# arduinoVisor.net
KiCad netlist of a schematic drawn in EAGLE
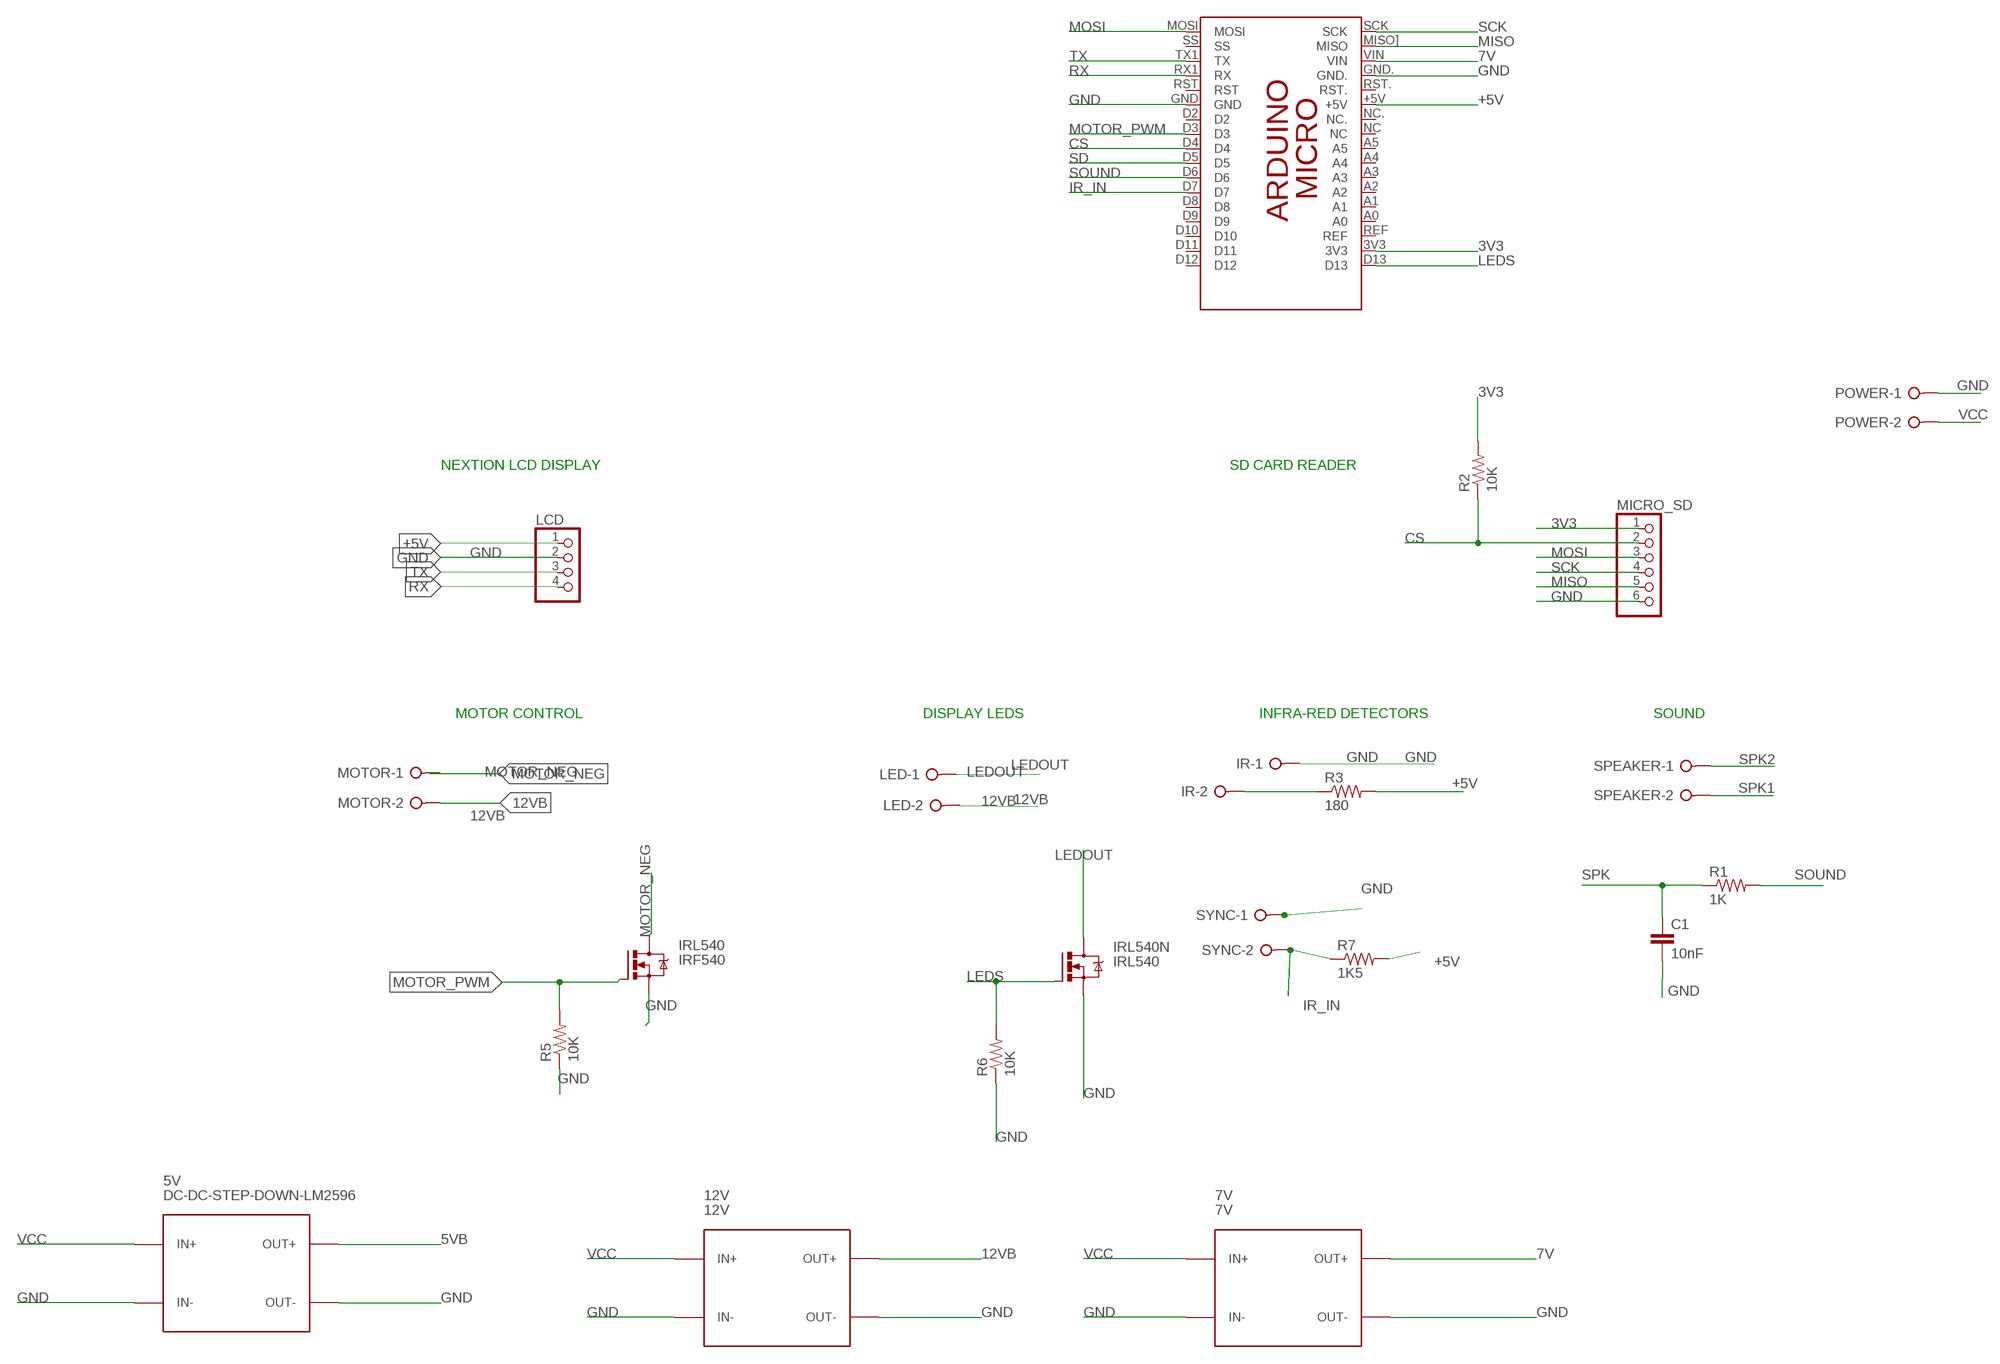
[diagram p0: schematic, sheet 1]
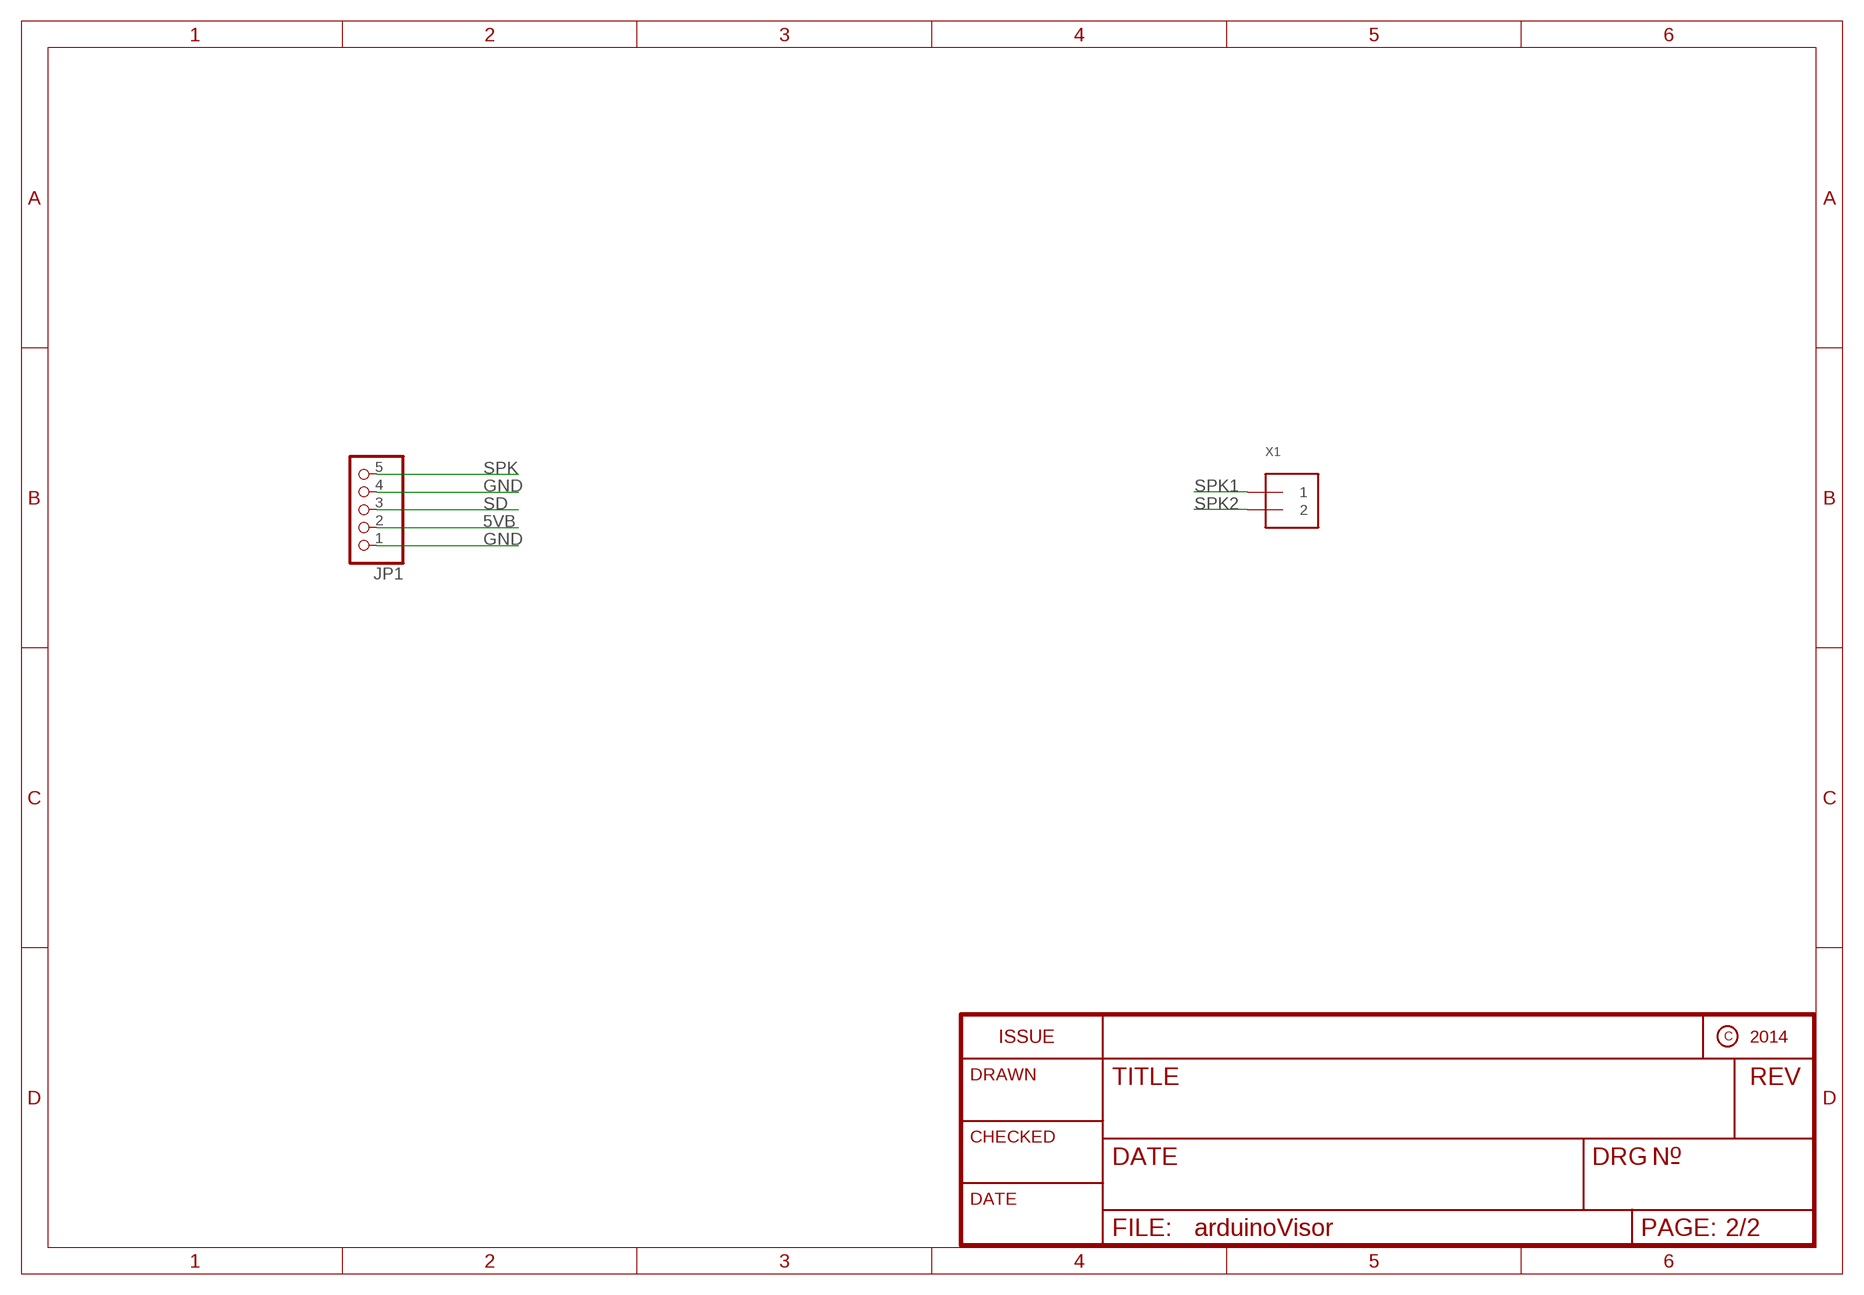
[diagram p1: schematic, sheet 2]

(export (version "E")
  (design (tool "Eeschema 10.0.6"))
  (components
    (comp (ref "JP1")
      (value "HEADER-1X570MIL")
      (footprint "eagle-import:1X05_ROUND_70")
      (libsource (lib "eagle-import") (part "HEADER-1X570MIL"))
    )
    (comp (ref "X1")
      (value "TERMBLOCK_1X2")
      (footprint "eagle-import:TERMBLOCK_1X2-3.5MM")
      (libsource (lib "eagle-import") (part "TERMBLOCK_1X2"))
    )
    (comp (ref "5V")
      (value "DC-DC-STEP-DOWN-LM2596")
      (footprint "eagle-import:DC-DC-STEP-DOWN-LM2596")
      (libsource (lib "eagle-import") (part "DC-DC-STEP-DOWN-LM2596"))
    )
    (comp (ref "7V")
      (value "7V")
      (footprint "eagle-import:DC-DC-STEP-DOWN-LM2596")
      (libsource (lib "eagle-import") (part "DC-DC-STEP-DOWN-LM2596"))
    )
    (comp (ref "12V")
      (value "12V")
      (footprint "eagle-import:DC-DC-STEP-DOWN-LM2596")
      (libsource (lib "eagle-import") (part "DC-DC-STEP-DOWN-LM2596"))
    )
    (comp (ref "C1")
      (value "10nF")
      (footprint "eagle-import:C2.5-2")
      (libsource (lib "eagle-import") (part "C2.5/2"))
    )
    (comp (ref "IR")
      (value "W237-02P")
      (footprint "eagle-import:W237-132")
      (libsource (lib "eagle-import") (part "W237-02P"))
    )
    (comp (ref "IRL540")
      (value "IRF540")
      (footprint "eagle-import:TO220BV")
      (libsource (lib "eagle-import") (part "IRF540"))
    )
    (comp (ref "IRL540N")
      (value "IRL540")
      (footprint "eagle-import:TO220BV")
      (libsource (lib "eagle-import") (part "IRF540"))
    )
    (comp (ref "LCD")
      (value "PINHD-1X4")
      (footprint "eagle-import:1X04")
      (libsource (lib "eagle-import") (part "PINHD-1X4"))
    )
    (comp (ref "LED")
      (value "W237-02P")
      (footprint "eagle-import:W237-132")
      (libsource (lib "eagle-import") (part "W237-02P"))
    )
    (comp (ref "MICRO_SD")
      (value "PINHD-1X6")
      (footprint "eagle-import:1X06")
      (libsource (lib "eagle-import") (part "PINHD-1X6"))
    )
    (comp (ref "MOTOR")
      (value "W237-02P")
      (footprint "eagle-import:W237-132")
      (libsource (lib "eagle-import") (part "W237-02P"))
    )
    (comp (ref "PCB2")
      (value "ARDUINO_MICRO")
      (footprint "eagle-import:ARDUINO_MICRO")
      (libsource (lib "eagle-import") (part "ARDUINO_MICRO"))
    )
    (comp (ref "POWER")
      (value "W237-02P")
      (footprint "eagle-import:W237-132")
      (libsource (lib "eagle-import") (part "W237-02P"))
    )
    (comp (ref "R1")
      (value "1K")
      (footprint "eagle-import:0207_10")
      (libsource (lib "eagle-import") (part "R-US_0207/10"))
    )
    (comp (ref "R2")
      (value "10K")
      (footprint "eagle-import:0207_10")
      (libsource (lib "eagle-import") (part "R-US_0207/10"))
    )
    (comp (ref "R3")
      (value "180")
      (footprint "eagle-import:0207_10")
      (libsource (lib "eagle-import") (part "R-US_0207/10"))
    )
    (comp (ref "R5")
      (value "10K")
      (footprint "eagle-import:0207_10")
      (libsource (lib "eagle-import") (part "R-US_0207/10"))
    )
    (comp (ref "R6")
      (value "10K")
      (footprint "eagle-import:0207_10")
      (libsource (lib "eagle-import") (part "R-US_0207/10"))
    )
    (comp (ref "R7")
      (value "1K5")
      (footprint "eagle-import:0207_10")
      (libsource (lib "eagle-import") (part "R-US_0207/10"))
    )
    (comp (ref "SPEAKER")
      (value "W237-02P")
      (footprint "eagle-import:W237-132")
      (libsource (lib "eagle-import") (part "W237-02P"))
    )
    (comp (ref "SYNC")
      (value "W237-02P")
      (footprint "eagle-import:W237-132")
      (libsource (lib "eagle-import") (part "W237-02P"))
    )
  )
  (nets
    (net (code "1") (name "+5V") (class "Default")
      (node (ref "LCD") (pin "1") (pinfunction "1_1") (pintype "passive"))
      (node (ref "PCB2") (pin "+5V") (pinfunction "+5V_+5V") (pintype "bidirectional"))
      (node (ref "R3") (pin "2") (pinfunction "2_2") (pintype "passive"))
      (node (ref "R7") (pin "2") (pinfunction "2_2") (pintype "passive"))
    )
    (net (code "2") (name "3V3") (class "Default")
      (node (ref "MICRO_SD") (pin "1") (pinfunction "1_1") (pintype "passive"))
      (node (ref "PCB2") (pin "3V3") (pinfunction "3V3_3V3") (pintype "bidirectional"))
      (node (ref "R2") (pin "2") (pinfunction "2_2") (pintype "passive"))
    )
    (net (code "3") (name "5VB") (class "Default")
      (node (ref "5V") (pin "OUT+") (pinfunction "OUT+_OUT+") (pintype "bidirectional"))
      (node (ref "JP1") (pin "2") (pinfunction "2_2") (pintype "passive"))
    )
    (net (code "4") (name "7V") (class "Default")
      (node (ref "7V") (pin "OUT+") (pinfunction "OUT+_OUT+") (pintype "bidirectional"))
      (node (ref "PCB2") (pin "VIN") (pinfunction "VIN_VIN") (pintype "bidirectional"))
    )
    (net (code "5") (name "12VB") (class "Default")
      (node (ref "12V") (pin "OUT+") (pinfunction "OUT+_OUT+") (pintype "bidirectional"))
      (node (ref "LED") (pin "2") (pinfunction "KL_2") (pintype "passive"))
      (node (ref "MOTOR") (pin "2") (pinfunction "KL_2") (pintype "passive"))
    )
    (net (code "6") (name "CS") (class "Default")
      (node (ref "MICRO_SD") (pin "2") (pinfunction "2_2") (pintype "passive"))
      (node (ref "PCB2") (pin "D4") (pinfunction "D4_D4") (pintype "bidirectional"))
      (node (ref "R2") (pin "1") (pinfunction "1_1") (pintype "passive"))
    )
    (net (code "7") (name "GND") (class "Default")
      (node (ref "12V") (pin "IN-") (pinfunction "IN-_IN-") (pintype "bidirectional"))
      (node (ref "12V") (pin "OUT-") (pinfunction "OUT-_OUT-") (pintype "bidirectional"))
      (node (ref "5V") (pin "IN-") (pinfunction "IN-_IN-") (pintype "bidirectional"))
      (node (ref "5V") (pin "OUT-") (pinfunction "OUT-_OUT-") (pintype "bidirectional"))
      (node (ref "7V") (pin "IN-") (pinfunction "IN-_IN-") (pintype "bidirectional"))
      (node (ref "7V") (pin "OUT-") (pinfunction "OUT-_OUT-") (pintype "bidirectional"))
      (node (ref "C1") (pin "2") (pinfunction "2_2") (pintype "passive"))
      (node (ref "IR") (pin "1") (pinfunction "KL_1") (pintype "passive"))
      (node (ref "IRL540") (pin "S") (pinfunction "S_S") (pintype "passive"))
      (node (ref "IRL540N") (pin "S") (pinfunction "S_S") (pintype "passive"))
      (node (ref "JP1") (pin "1") (pinfunction "1_1") (pintype "passive"))
      (node (ref "JP1") (pin "4") (pinfunction "4_4") (pintype "passive"))
      (node (ref "LCD") (pin "2") (pinfunction "2_2") (pintype "passive"))
      (node (ref "MICRO_SD") (pin "6") (pinfunction "6_6") (pintype "passive"))
      (node (ref "PCB2") (pin "GND") (pinfunction "GND_GND") (pintype "bidirectional"))
      (node (ref "PCB2") (pin "GND.") (pinfunction "GND._GND.") (pintype "bidirectional"))
      (node (ref "POWER") (pin "1") (pinfunction "KL_1") (pintype "passive"))
      (node (ref "R5") (pin "1") (pinfunction "1_1") (pintype "passive"))
      (node (ref "R6") (pin "1") (pinfunction "1_1") (pintype "passive"))
      (node (ref "SYNC") (pin "1") (pinfunction "KL_1") (pintype "passive"))
    )
    (net (code "8") (name "IR_IN") (class "Default")
      (node (ref "PCB2") (pin "D7") (pinfunction "D7_D7") (pintype "bidirectional"))
      (node (ref "R7") (pin "1") (pinfunction "1_1") (pintype "passive"))
      (node (ref "SYNC") (pin "2") (pinfunction "KL_2") (pintype "passive"))
    )
    (net (code "9") (name "LEDOUT") (class "Default")
      (node (ref "IRL540N") (pin "D") (pinfunction "D_D") (pintype "passive"))
      (node (ref "LED") (pin "1") (pinfunction "KL_1") (pintype "passive"))
    )
    (net (code "10") (name "LEDS") (class "Default")
      (node (ref "IRL540N") (pin "G") (pinfunction "G_G") (pintype "passive"))
      (node (ref "PCB2") (pin "D13") (pinfunction "D13_D13") (pintype "bidirectional"))
      (node (ref "R6") (pin "2") (pinfunction "2_2") (pintype "passive"))
    )
    (net (code "11") (name "MISO") (class "Default")
      (node (ref "MICRO_SD") (pin "5") (pinfunction "5_5") (pintype "passive"))
      (node (ref "PCB2") (pin "MISO]") (pinfunction "MISO_MISO]") (pintype "bidirectional"))
    )
    (net (code "12") (name "MOSI") (class "Default")
      (node (ref "MICRO_SD") (pin "3") (pinfunction "3_3") (pintype "passive"))
      (node (ref "PCB2") (pin "MOSI") (pinfunction "MOSI_MOSI") (pintype "bidirectional"))
    )
    (net (code "13") (name "MOTOR_NEG") (class "Default")
      (node (ref "IRL540") (pin "D") (pinfunction "D_D") (pintype "passive"))
      (node (ref "MOTOR") (pin "1") (pinfunction "KL_1") (pintype "passive"))
    )
    (net (code "14") (name "MOTOR_PWM") (class "Default")
      (node (ref "IRL540") (pin "G") (pinfunction "G_G") (pintype "passive"))
      (node (ref "PCB2") (pin "D3") (pinfunction "D3_D3") (pintype "bidirectional"))
      (node (ref "R5") (pin "2") (pinfunction "2_2") (pintype "passive"))
    )
    (net (code "15") (name "Net-(IRB-KL)") (class "Default")
      (node (ref "IR") (pin "2") (pinfunction "KL_2") (pintype "passive"))
      (node (ref "R3") (pin "1") (pinfunction "1_1") (pintype "passive"))
    )
    (net (code "16") (name "RX") (class "Default")
      (node (ref "LCD") (pin "4") (pinfunction "4_4") (pintype "passive"))
      (node (ref "PCB2") (pin "RX1") (pinfunction "RX_RX1") (pintype "bidirectional"))
    )
    (net (code "17") (name "SCK") (class "Default")
      (node (ref "MICRO_SD") (pin "4") (pinfunction "4_4") (pintype "passive"))
      (node (ref "PCB2") (pin "SCK") (pinfunction "SCK_SCK") (pintype "bidirectional"))
    )
    (net (code "18") (name "SD") (class "Default")
      (node (ref "JP1") (pin "3") (pinfunction "3_3") (pintype "passive"))
      (node (ref "PCB2") (pin "D5") (pinfunction "D5_D5") (pintype "bidirectional"))
    )
    (net (code "19") (name "SOUND") (class "Default")
      (node (ref "PCB2") (pin "D6") (pinfunction "D6_D6") (pintype "bidirectional"))
      (node (ref "R1") (pin "2") (pinfunction "2_2") (pintype "passive"))
    )
    (net (code "20") (name "SPK") (class "Default")
      (node (ref "C1") (pin "1") (pinfunction "1_1") (pintype "passive"))
      (node (ref "JP1") (pin "5") (pinfunction "5_5") (pintype "passive"))
      (node (ref "R1") (pin "1") (pinfunction "1_1") (pintype "passive"))
    )
    (net (code "21") (name "SPK1") (class "Default")
      (node (ref "SPEAKER") (pin "2") (pinfunction "KL_2") (pintype "passive"))
      (node (ref "X1") (pin "1") (pinfunction "1_1") (pintype "passive"))
    )
    (net (code "22") (name "SPK2") (class "Default")
      (node (ref "SPEAKER") (pin "1") (pinfunction "KL_1") (pintype "passive"))
      (node (ref "X1") (pin "2") (pinfunction "2_2") (pintype "passive"))
    )
    (net (code "23") (name "TX") (class "Default")
      (node (ref "LCD") (pin "3") (pinfunction "3_3") (pintype "passive"))
      (node (ref "PCB2") (pin "TX1") (pinfunction "TX_TX1") (pintype "bidirectional"))
    )
    (net (code "24") (name "VCC") (class "Default")
      (node (ref "12V") (pin "IN+") (pinfunction "IN+_IN+") (pintype "bidirectional"))
      (node (ref "5V") (pin "IN+") (pinfunction "IN+_IN+") (pintype "bidirectional"))
      (node (ref "7V") (pin "IN+") (pinfunction "IN+_IN+") (pintype "bidirectional"))
      (node (ref "POWER") (pin "2") (pinfunction "KL_2") (pintype "passive"))
    )
    (net (code "25") (name "unconnected-(PCB2-PadA0)") (class "Default")
      (node (ref "PCB2") (pin "A0") (pinfunction "A0_A0") (pintype "bidirectional"))
    )
    (net (code "26") (name "unconnected-(PCB2-PadA1)") (class "Default")
      (node (ref "PCB2") (pin "A1") (pinfunction "A1_A1") (pintype "bidirectional"))
    )
    (net (code "27") (name "unconnected-(PCB2-PadA2)") (class "Default")
      (node (ref "PCB2") (pin "A2") (pinfunction "A2_A2") (pintype "bidirectional"))
    )
    (net (code "28") (name "unconnected-(PCB2-PadA3)") (class "Default")
      (node (ref "PCB2") (pin "A3") (pinfunction "A3_A3") (pintype "bidirectional"))
    )
    (net (code "29") (name "unconnected-(PCB2-PadA4)") (class "Default")
      (node (ref "PCB2") (pin "A4") (pinfunction "A4_A4") (pintype "bidirectional"))
    )
    (net (code "30") (name "unconnected-(PCB2-PadA5)") (class "Default")
      (node (ref "PCB2") (pin "A5") (pinfunction "A5_A5") (pintype "bidirectional"))
    )
    (net (code "31") (name "unconnected-(PCB2-PadD2)") (class "Default")
      (node (ref "PCB2") (pin "D2") (pinfunction "D2_D2") (pintype "bidirectional"))
    )
    (net (code "32") (name "unconnected-(PCB2-PadD8)") (class "Default")
      (node (ref "PCB2") (pin "D8") (pinfunction "D8_D8") (pintype "bidirectional"))
    )
    (net (code "33") (name "unconnected-(PCB2-PadD9)") (class "Default")
      (node (ref "PCB2") (pin "D9") (pinfunction "D9_D9") (pintype "bidirectional"))
    )
    (net (code "34") (name "unconnected-(PCB2-PadD10)") (class "Default")
      (node (ref "PCB2") (pin "D10") (pinfunction "D10_D10") (pintype "bidirectional"))
    )
    (net (code "35") (name "unconnected-(PCB2-PadD11)") (class "Default")
      (node (ref "PCB2") (pin "D11") (pinfunction "D11_D11") (pintype "bidirectional"))
    )
    (net (code "36") (name "unconnected-(PCB2-PadD12)") (class "Default")
      (node (ref "PCB2") (pin "D12") (pinfunction "D12_D12") (pintype "bidirectional"))
    )
    (net (code "37") (name "unconnected-(PCB2-PadNC)") (class "Default")
      (node (ref "PCB2") (pin "NC") (pinfunction "NC_NC") (pintype "bidirectional"))
    )
    (net (code "38") (name "unconnected-(PCB2-PadNC.)") (class "Default")
      (node (ref "PCB2") (pin "NC.") (pinfunction "NC._NC.") (pintype "bidirectional"))
    )
    (net (code "39") (name "unconnected-(PCB2-PadREF)") (class "Default")
      (node (ref "PCB2") (pin "REF") (pinfunction "REF_REF") (pintype "bidirectional"))
    )
    (net (code "40") (name "unconnected-(PCB2-PadRST)") (class "Default")
      (node (ref "PCB2") (pin "RST") (pinfunction "RST_RST") (pintype "bidirectional"))
    )
    (net (code "41") (name "unconnected-(PCB2-PadRST.)") (class "Default")
      (node (ref "PCB2") (pin "RST.") (pinfunction "RST._RST.") (pintype "bidirectional"))
    )
    (net (code "42") (name "unconnected-(PCB2-PadSS)") (class "Default")
      (node (ref "PCB2") (pin "SS") (pinfunction "SS_SS") (pintype "bidirectional"))
    )
  )
)
